# ELEC3300_DAP.net
KiCad netlist of a schematic drawn in Altium Designer
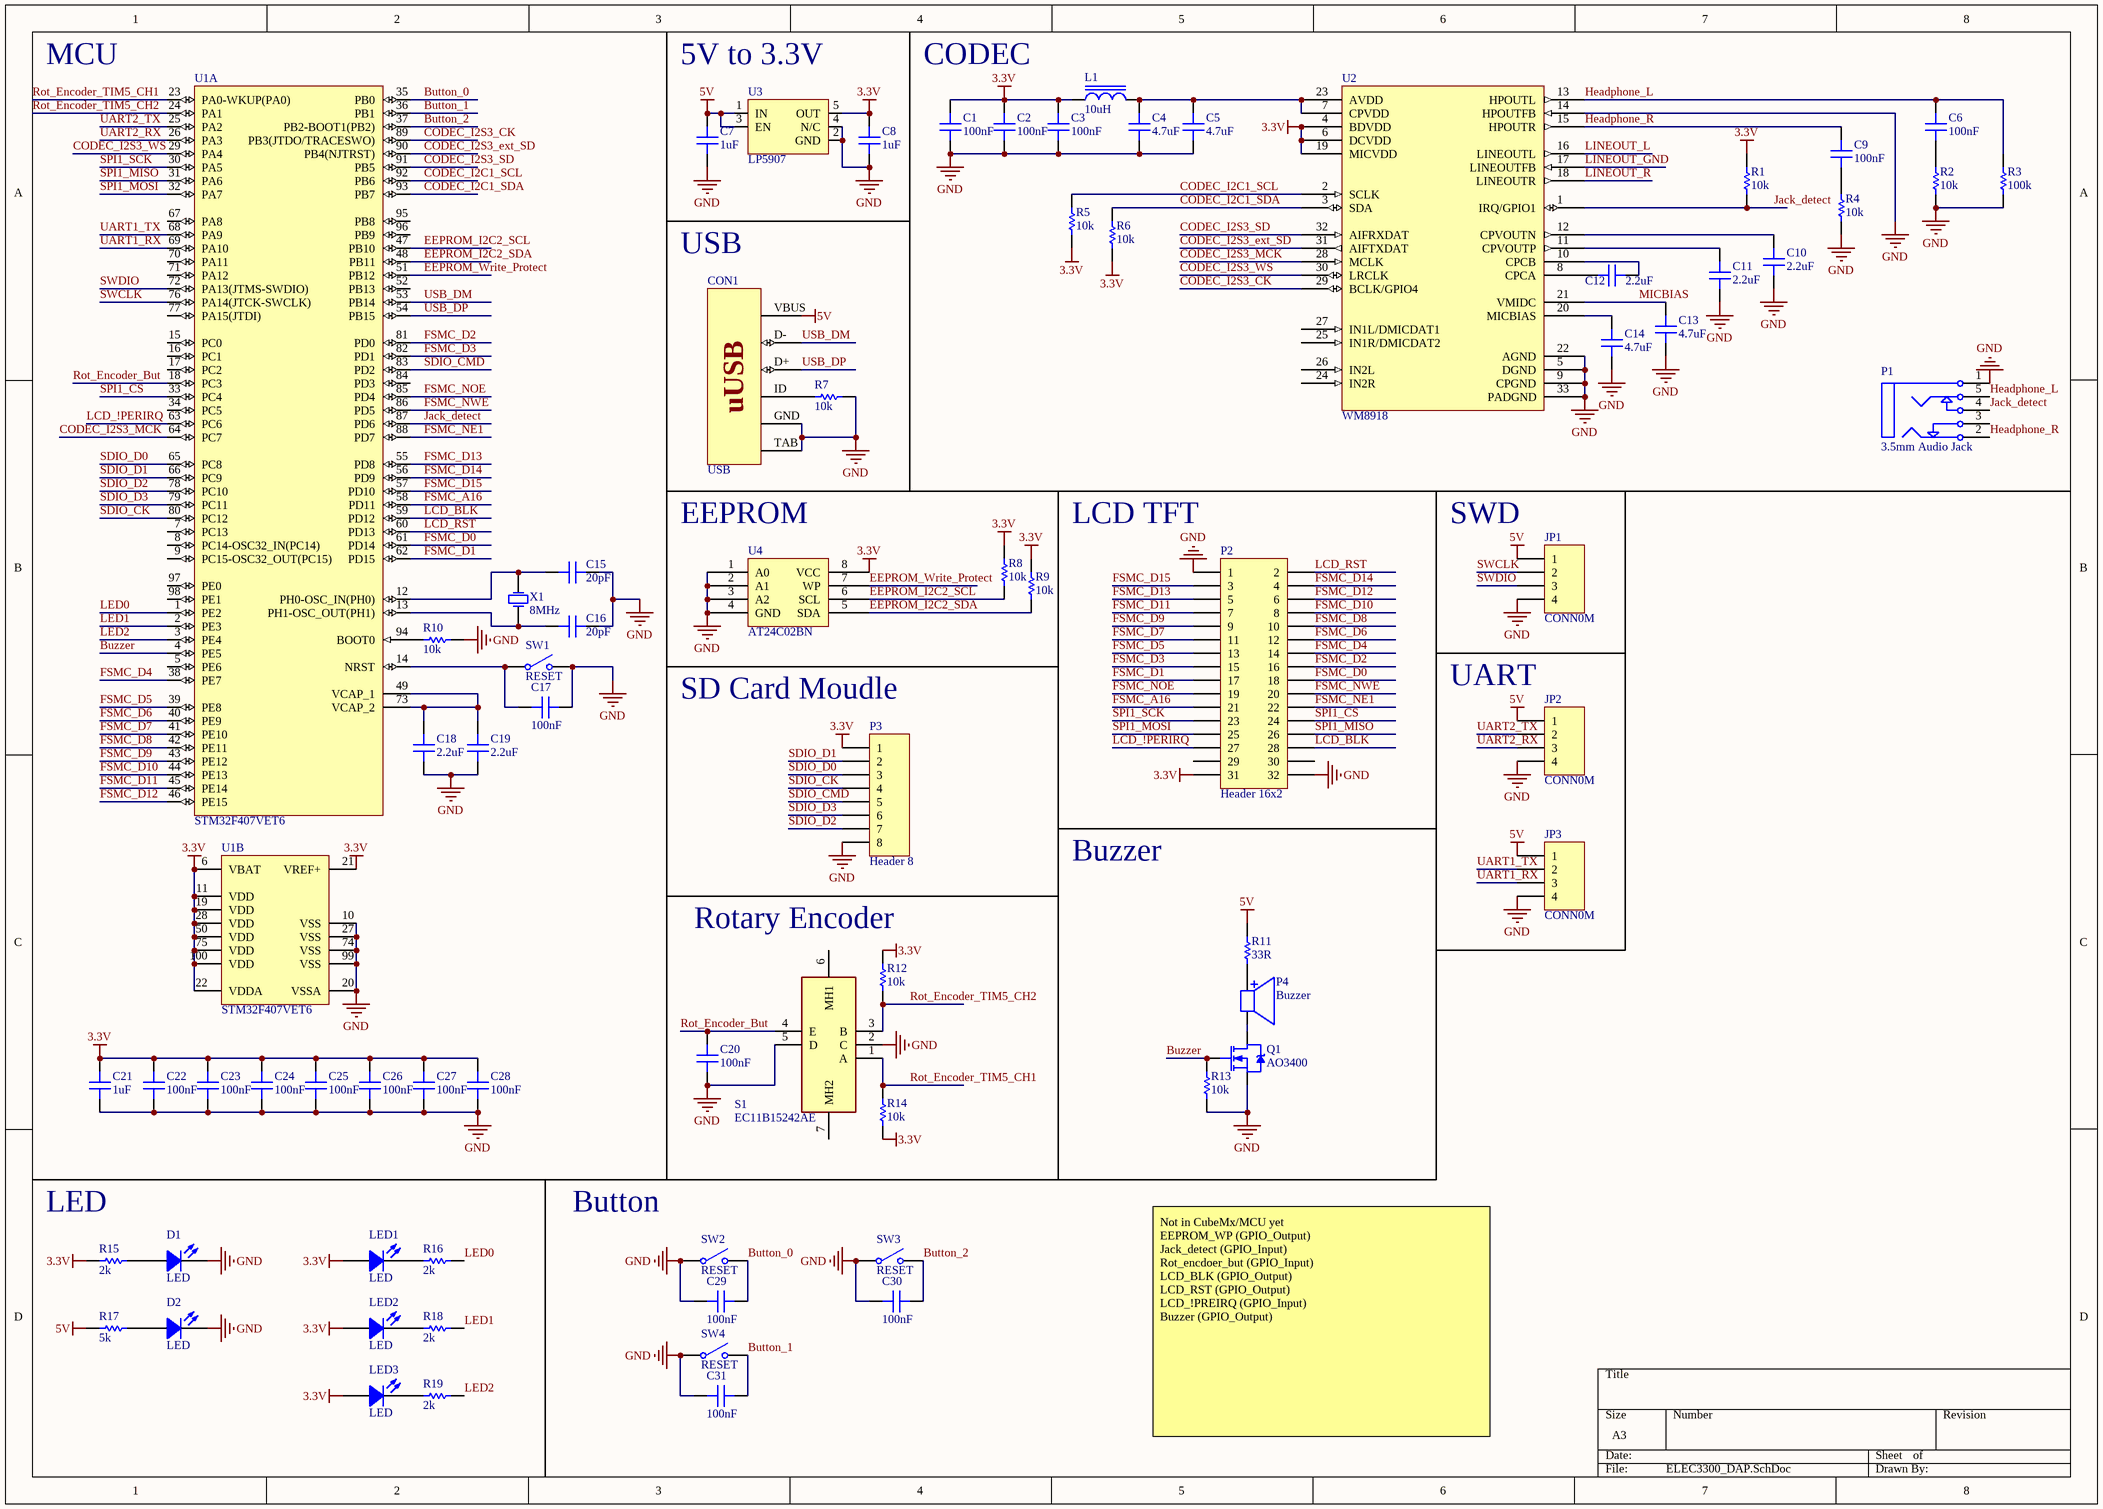
[diagram p0: ELEC3300_DAP.SchDoc]

(export (version "E")
  (design (tool "Eeschema 10.0.6"))
  (components
    (comp (ref "C1")
      (value "100nF")
      (footprint "CC2012-0805")
      (description "Capacitor (Semiconductor SIM Model)")
      (fields (field (name "PUBLISHER") "Altium Limited"))
      (libsource (lib "Robocon_RCL") (part "Cap Semi"))
    )
    (comp (ref "C2")
      (value "100nF")
      (footprint "CC2012-0805")
      (description "Capacitor (Semiconductor SIM Model)")
      (fields (field (name "PUBLISHER") "Altium Limited"))
      (libsource (lib "Robocon_RCL") (part "Cap Semi"))
    )
    (comp (ref "C3")
      (value "100nF")
      (footprint "CC2012-0805")
      (description "Capacitor (Semiconductor SIM Model)")
      (fields (field (name "PUBLISHER") "Altium Limited"))
      (libsource (lib "Robocon_RCL") (part "Cap Semi"))
    )
    (comp (ref "C4")
      (value "4.7uF")
      (footprint "CC2012-0805")
      (description "Capacitor (Semiconductor SIM Model)")
      (fields (field (name "PUBLISHER") "Altium Limited"))
      (libsource (lib "Robocon_RCL") (part "Cap Semi"))
    )
    (comp (ref "C5")
      (value "4.7uF")
      (footprint "CC2012-0805")
      (description "Capacitor (Semiconductor SIM Model)")
      (fields (field (name "PUBLISHER") "Altium Limited"))
      (libsource (lib "Robocon_RCL") (part "Cap Semi"))
    )
    (comp (ref "C6")
      (value "100nF")
      (footprint "CC2012-0805")
      (description "Capacitor (Semiconductor SIM Model)")
      (fields (field (name "PUBLISHER") "Altium Limited"))
      (libsource (lib "Robocon_RCL") (part "Cap Semi"))
    )
    (comp (ref "C7")
      (value "1uF")
      (footprint "CC2012-0805")
      (description "Capacitor (Semiconductor SIM Model)")
      (fields (field (name "PUBLISHER") "Altium Limited"))
      (libsource (lib "Robocon_RCL") (part "Cap Semi"))
    )
    (comp (ref "C8")
      (value "1uF")
      (footprint "CC2012-0805")
      (description "Capacitor (Semiconductor SIM Model)")
      (fields (field (name "PUBLISHER") "Altium Limited"))
      (libsource (lib "Robocon_RCL") (part "Cap Semi"))
    )
    (comp (ref "C9")
      (value "100nF")
      (footprint "CC2012-0805")
      (description "Capacitor (Semiconductor SIM Model)")
      (fields (field (name "PUBLISHER") "Altium Limited"))
      (libsource (lib "Robocon_RCL") (part "Cap Semi"))
    )
    (comp (ref "C10")
      (value "2.2uF")
      (footprint "CC2012-0805")
      (description "Capacitor (Semiconductor SIM Model)")
      (fields (field (name "PUBLISHER") "Altium Limited"))
      (libsource (lib "Robocon_RCL") (part "Cap Semi"))
    )
    (comp (ref "C11")
      (value "2.2uF")
      (footprint "CC2012-0805")
      (description "Capacitor (Semiconductor SIM Model)")
      (fields (field (name "PUBLISHER") "Altium Limited"))
      (libsource (lib "Robocon_RCL") (part "Cap Semi"))
    )
    (comp (ref "C12")
      (value "2.2uF")
      (footprint "CC2012-0805")
      (description "Capacitor (Semiconductor SIM Model)")
      (fields (field (name "PUBLISHER") "Altium Limited"))
      (libsource (lib "Robocon_RCL") (part "Cap Semi"))
    )
    (comp (ref "C13")
      (value "4.7uF")
      (footprint "CC2012-0805")
      (description "Capacitor (Semiconductor SIM Model)")
      (fields (field (name "PUBLISHER") "Altium Limited"))
      (libsource (lib "Robocon_RCL") (part "Cap Semi"))
    )
    (comp (ref "C14")
      (value "4.7uF")
      (footprint "CC2012-0805")
      (description "Capacitor (Semiconductor SIM Model)")
      (fields (field (name "PUBLISHER") "Altium Limited"))
      (libsource (lib "Robocon_RCL") (part "Cap Semi"))
    )
    (comp (ref "C15")
      (value "20pF")
      (footprint "CC2012-0805")
      (description "Capacitor (Semiconductor SIM Model)")
      (fields (field (name "PUBLISHER") "Altium Limited"))
      (libsource (lib "Robocon_RCL") (part "Cap Semi"))
    )
    (comp (ref "C16")
      (value "20pF")
      (footprint "CC2012-0805")
      (description "Capacitor (Semiconductor SIM Model)")
      (fields (field (name "PUBLISHER") "Altium Limited"))
      (libsource (lib "Robocon_RCL") (part "Cap Semi"))
    )
    (comp (ref "C17")
      (value "100nF")
      (footprint "CC2012-0805")
      (description "Capacitor (Semiconductor SIM Model)")
      (fields (field (name "PUBLISHER") "Altium Limited"))
      (libsource (lib "Robocon_RCL") (part "Cap Semi"))
    )
    (comp (ref "C18")
      (value "2.2uF")
      (footprint "CC2012-0805")
      (description "Capacitor (Semiconductor SIM Model)")
      (fields (field (name "PUBLISHER") "Altium Limited"))
      (libsource (lib "Robocon_RCL") (part "Cap Semi"))
    )
    (comp (ref "C19")
      (value "2.2uF")
      (footprint "CC2012-0805")
      (description "Capacitor (Semiconductor SIM Model)")
      (fields (field (name "PUBLISHER") "Altium Limited"))
      (libsource (lib "Robocon_RCL") (part "Cap Semi"))
    )
    (comp (ref "C20")
      (value "100nF")
      (footprint "CC2012-0805")
      (description "Capacitor (Semiconductor SIM Model)")
      (fields (field (name "PUBLISHER") "Altium Limited"))
      (libsource (lib "Robocon_RCL") (part "Cap Semi"))
    )
    (comp (ref "C21")
      (value "1uF")
      (footprint "CC2012-0805")
      (description "Capacitor (Semiconductor SIM Model)")
      (fields (field (name "PUBLISHER") "Altium Limited"))
      (libsource (lib "Robocon_RCL") (part "Cap Semi"))
    )
    (comp (ref "C22")
      (value "100nF")
      (footprint "CC2012-0805")
      (description "Capacitor (Semiconductor SIM Model)")
      (fields (field (name "PUBLISHER") "Altium Limited"))
      (libsource (lib "Robocon_RCL") (part "Cap Semi"))
    )
    (comp (ref "C23")
      (value "100nF")
      (footprint "CC2012-0805")
      (description "Capacitor (Semiconductor SIM Model)")
      (fields (field (name "PUBLISHER") "Altium Limited"))
      (libsource (lib "Robocon_RCL") (part "Cap Semi"))
    )
    (comp (ref "C24")
      (value "100nF")
      (footprint "CC2012-0805")
      (description "Capacitor (Semiconductor SIM Model)")
      (fields (field (name "PUBLISHER") "Altium Limited"))
      (libsource (lib "Robocon_RCL") (part "Cap Semi"))
    )
    (comp (ref "C25")
      (value "100nF")
      (footprint "CC2012-0805")
      (description "Capacitor (Semiconductor SIM Model)")
      (fields (field (name "PUBLISHER") "Altium Limited"))
      (libsource (lib "Robocon_RCL") (part "Cap Semi"))
    )
    (comp (ref "C26")
      (value "100nF")
      (footprint "CC2012-0805")
      (description "Capacitor (Semiconductor SIM Model)")
      (fields (field (name "PUBLISHER") "Altium Limited"))
      (libsource (lib "Robocon_RCL") (part "Cap Semi"))
    )
    (comp (ref "C27")
      (value "100nF")
      (footprint "CC2012-0805")
      (description "Capacitor (Semiconductor SIM Model)")
      (fields (field (name "PUBLISHER") "Altium Limited"))
      (libsource (lib "Robocon_RCL") (part "Cap Semi"))
    )
    (comp (ref "C28")
      (value "100nF")
      (footprint "CC2012-0805")
      (description "Capacitor (Semiconductor SIM Model)")
      (fields (field (name "PUBLISHER") "Altium Limited"))
      (libsource (lib "Robocon_RCL") (part "Cap Semi"))
    )
    (comp (ref "C29")
      (value "100nF")
      (footprint "CC2012-0805")
      (description "Capacitor (Semiconductor SIM Model)")
      (fields (field (name "PUBLISHER") "Altium Limited"))
      (libsource (lib "Robocon_RCL") (part "Cap Semi"))
    )
    (comp (ref "C30")
      (value "100nF")
      (footprint "CC2012-0805")
      (description "Capacitor (Semiconductor SIM Model)")
      (fields (field (name "PUBLISHER") "Altium Limited"))
      (libsource (lib "Robocon_RCL") (part "Cap Semi"))
    )
    (comp (ref "C31")
      (value "100nF")
      (footprint "CC2012-0805")
      (description "Capacitor (Semiconductor SIM Model)")
      (fields (field (name "PUBLISHER") "Altium Limited"))
      (libsource (lib "Robocon_RCL") (part "Cap Semi"))
    )
    (comp (ref "CON1")
      (value "USB")
      (footprint "USB-UB-S-HML")
      (libsource (lib "Robocon_connectors") (part "USB Series Micro-B"))
    )
    (comp (ref "D1")
      (value "LED")
      (footprint "D0805")
      (description "Typical RED GaAs LED")
      (fields (field (name "PUBLISHER") "Altium Limited"))
      (libsource (lib "Robocon_BJT") (part "LED"))
    )
    (comp (ref "D2")
      (value "LED")
      (footprint "D0805")
      (description "Typical RED GaAs LED")
      (fields (field (name "PUBLISHER") "Altium Limited"))
      (libsource (lib "Robocon_BJT") (part "LED"))
    )
    (comp (ref "JP1")
      (value "CONN0M")
      (footprint "LOCKEDHDR-4W")
      (description "Header, 4-Pin")
      (fields (field (name "PUBLISHER") "Altium Limited"))
      (libsource (lib "Robocon_connectors") (part "Header 4"))
    )
    (comp (ref "JP2")
      (value "CONN0M")
      (footprint "LOCKEDHDR-4W")
      (description "Header, 4-Pin")
      (fields (field (name "PUBLISHER") "Altium Limited"))
      (libsource (lib "Robocon_connectors") (part "Header 4"))
    )
    (comp (ref "JP3")
      (value "CONN0M")
      (footprint "LOCKEDHDR-4W")
      (description "Header, 4-Pin")
      (fields (field (name "PUBLISHER") "Altium Limited"))
      (libsource (lib "Robocon_connectors") (part "Header 4"))
    )
    (comp (ref "L1")
      (value "10uH")
      (footprint "CL2012-0805")
      (description "Inductor")
      (fields (field (name "PUBLISHER") "Altium Limited"))
      (libsource (lib "Robocon_RCL") (part "Inductor"))
    )
    (comp (ref "LED1")
      (value "LED")
      (footprint "D0805")
      (description "Typical RED GaAs LED")
      (fields (field (name "PUBLISHER") "Altium Limited"))
      (libsource (lib "Robocon_BJT") (part "LED"))
    )
    (comp (ref "LED2")
      (value "LED")
      (footprint "D0805")
      (description "Typical RED GaAs LED")
      (fields (field (name "PUBLISHER") "Altium Limited"))
      (libsource (lib "Robocon_BJT") (part "LED"))
    )
    (comp (ref "LED3")
      (value "LED")
      (footprint "D0805")
      (description "Typical RED GaAs LED")
      (fields (field (name "PUBLISHER") "Altium Limited"))
      (libsource (lib "Robocon_BJT") (part "LED"))
    )
    (comp (ref "P1")
      (value "3.5mm Audio Jack")
      (footprint "STX-3120-5B")
      (description "Conductor Jack with 2 break contacts (normals) and 2 auxiliary make contacts")
      (libsource (lib "Robocon_connectors") (part "Audio Jack 3P"))
    )
    (comp (ref "P2")
      (value "Header 16x2")
      (footprint "HDR2X16")
      (libsource (lib "Schlib1") (part "Header 16x2"))
    )
    (comp (ref "P3")
      (value "Header 8")
      (footprint "HDR1X8")
      (description "Header, 8-Pin")
      (fields (field (name "PUBLISHER") "Altium Limited"))
      (libsource (lib "Robocon_connectors") (part "Header 8"))
    )
    (comp (ref "P4") (value "Buzzer") (footprint "BUZ-9.0") (libsource (lib "Robocon_RCL") (part "Buzzer")))
    (comp (ref "Q1")
      (value "AO3400")
      (footprint "SO-G3/Z3.3")
      (description "N-Channel MOSFET")
      (fields (field (name "PUBLISHER") "Altium Limited"))
      (libsource (lib "Robocon_BJT") (part "AO3400"))
    )
    (comp (ref "R1")
      (value "10k")
      (footprint "CR2012-0805")
      (description "Semiconductor Resistor")
      (fields (field (name "PUBLISHER") "Altium Limited"))
      (libsource (lib "Robocon_RCL") (part "Res Semi"))
    )
    (comp (ref "R2")
      (value "10k")
      (footprint "CR2012-0805")
      (description "Semiconductor Resistor")
      (fields (field (name "PUBLISHER") "Altium Limited"))
      (libsource (lib "Robocon_RCL") (part "Res Semi"))
    )
    (comp (ref "R3")
      (value "100k")
      (footprint "CR2012-0805")
      (description "Semiconductor Resistor")
      (fields (field (name "PUBLISHER") "Altium Limited"))
      (libsource (lib "Robocon_RCL") (part "Res Semi"))
    )
    (comp (ref "R4")
      (value "10k")
      (footprint "CR2012-0805")
      (description "Semiconductor Resistor")
      (fields (field (name "PUBLISHER") "Altium Limited"))
      (libsource (lib "Robocon_RCL") (part "Res Semi"))
    )
    (comp (ref "R5")
      (value "10k")
      (footprint "CR2012-0805")
      (description "Semiconductor Resistor")
      (fields (field (name "PUBLISHER") "Altium Limited"))
      (libsource (lib "Robocon_RCL") (part "Res Semi"))
    )
    (comp (ref "R6")
      (value "10k")
      (footprint "CR2012-0805")
      (description "Semiconductor Resistor")
      (fields (field (name "PUBLISHER") "Altium Limited"))
      (libsource (lib "Robocon_RCL") (part "Res Semi"))
    )
    (comp (ref "R7")
      (value "10k")
      (footprint "CR2012-0805")
      (description "Semiconductor Resistor")
      (fields (field (name "PUBLISHER") "Altium Limited"))
      (libsource (lib "Robocon_RCL") (part "Res Semi"))
    )
    (comp (ref "R8")
      (value "10k")
      (footprint "CR2012-0805")
      (description "Semiconductor Resistor")
      (fields (field (name "PUBLISHER") "Altium Limited"))
      (libsource (lib "Robocon_RCL") (part "Res Semi"))
    )
    (comp (ref "R9")
      (value "10k")
      (footprint "CR2012-0805")
      (description "Semiconductor Resistor")
      (fields (field (name "PUBLISHER") "Altium Limited"))
      (libsource (lib "Robocon_RCL") (part "Res Semi"))
    )
    (comp (ref "R10")
      (value "10k")
      (footprint "CR2012-0805")
      (description "Semiconductor Resistor")
      (fields (field (name "PUBLISHER") "Altium Limited"))
      (libsource (lib "Robocon_RCL") (part "Res Semi"))
    )
    (comp (ref "R11")
      (value "33R")
      (footprint "CR2012-0805")
      (description "Semiconductor Resistor")
      (fields (field (name "PUBLISHER") "Altium Limited"))
      (libsource (lib "Robocon_RCL") (part "Res Semi"))
    )
    (comp (ref "R12")
      (value "10k")
      (footprint "CR2012-0805")
      (description "Semiconductor Resistor")
      (fields (field (name "PUBLISHER") "Altium Limited"))
      (libsource (lib "Robocon_RCL") (part "Res Semi"))
    )
    (comp (ref "R13")
      (value "10k")
      (footprint "CR2012-0805")
      (description "Semiconductor Resistor")
      (fields (field (name "PUBLISHER") "Altium Limited"))
      (libsource (lib "Robocon_RCL") (part "Res Semi"))
    )
    (comp (ref "R14")
      (value "10k")
      (footprint "CR2012-0805")
      (description "Semiconductor Resistor")
      (fields (field (name "PUBLISHER") "Altium Limited"))
      (libsource (lib "Robocon_RCL") (part "Res Semi"))
    )
    (comp (ref "R15")
      (value "2k")
      (footprint "CR2012-0805")
      (description "Semiconductor Resistor")
      (fields (field (name "PUBLISHER") "Altium Limited"))
      (libsource (lib "Robocon_RCL") (part "Res Semi"))
    )
    (comp (ref "R16")
      (value "2k")
      (footprint "CR2012-0805")
      (description "Semiconductor Resistor")
      (fields (field (name "PUBLISHER") "Altium Limited"))
      (libsource (lib "Robocon_RCL") (part "Res Semi"))
    )
    (comp (ref "R17")
      (value "5k")
      (footprint "CR2012-0805")
      (description "Semiconductor Resistor")
      (fields (field (name "PUBLISHER") "Altium Limited"))
      (libsource (lib "Robocon_RCL") (part "Res Semi"))
    )
    (comp (ref "R18")
      (value "2k")
      (footprint "CR2012-0805")
      (description "Semiconductor Resistor")
      (fields (field (name "PUBLISHER") "Altium Limited"))
      (libsource (lib "Robocon_RCL") (part "Res Semi"))
    )
    (comp (ref "R19")
      (value "2k")
      (footprint "CR2012-0805")
      (description "Semiconductor Resistor")
      (fields (field (name "PUBLISHER") "Altium Limited"))
      (libsource (lib "Robocon_RCL") (part "Res Semi"))
    )
    (comp (ref "S1")
      (value "EC11B15242AE")
      (footprint "EC11B15242AE")
      (description "Switch")
      (fields (field (name "MOUSER PART NUMBER") "688-EC11B15242AE"))
      (libsource (lib "Schlib1") (part "EC11B15242AE"))
    )
    (comp (ref "SW1")
      (value "RESET")
      (footprint "PUSH SWITCH 2-PIN")
      (description "Single-Pole, Single-Throw Switch")
      (fields (field (name "PUBLISHER") "Altium Limited"))
      (libsource (lib "Robocon_connectors") (part "SW-SPST"))
    )
    (comp (ref "SW2")
      (value "RESET")
      (footprint "PUSH SWITCH")
      (description "Single-Pole, Single-Throw Switch")
      (fields (field (name "PUBLISHER") "Altium Limited"))
      (libsource (lib "Robocon_connectors") (part "SW-SPST"))
    )
    (comp (ref "SW3")
      (value "RESET")
      (footprint "PUSH SWITCH")
      (description "Single-Pole, Single-Throw Switch")
      (fields (field (name "PUBLISHER") "Altium Limited"))
      (libsource (lib "Robocon_connectors") (part "SW-SPST"))
    )
    (comp (ref "SW4")
      (value "RESET")
      (footprint "PUSH SWITCH")
      (description "Single-Pole, Single-Throw Switch")
      (fields (field (name "PUBLISHER") "Altium Limited"))
      (libsource (lib "Robocon_connectors") (part "SW-SPST"))
    )
    (comp (ref "U1")
      (value "STM32F407VET6")
      (footprint "STM-LQFP100_N")
      (fields (field (name "MANUFACTURER") "STMicroelectronics"))
      (libsource (lib "STMicroelectronics STM32 F4") (part "STM32F407VET6"))
    )
    (comp (ref "U2")
      (value "WM8918")
      (footprint "QFN40P400X400X80-33N")
      (libsource (lib "Schlib1") (part "WM8918"))
    )
    (comp (ref "U3")
      (value "LP5907")
      (footprint "SOT-23-5")
      (description "LDO\r\nInput: 2.2V to 5.5V\r\nOutput: 3.3V 250mA\r\nEnable: high volt-> turns on")
      (libsource (lib "Robocon_IC") (part "LP5907"))
    )
    (comp (ref "U4")
      (value "AT24C02BN")
      (footprint "SOP-8")
      (description "Two-wire Serial EEPROM")
      (libsource (lib "Schlib1") (part "AT24C02BN"))
    )
    (comp (ref "X1")
      (value "8MHz")
      (footprint "BCY-W2/E4.7")
      (description "Crystal Oscillator")
      (fields (field (name "PUBLISHER") "Altium Limited"))
      (libsource (lib "Robocon_RCL") (part "XTAL"))
    )
  )
  (nets
    (net (code "1") (name "/Button_0") (class "Default")
      (node (ref "C29") (pin "1") (pinfunction "1_1") (pintype "passive"))
      (node (ref "SW2") (pin "2") (pinfunction "NO_2") (pintype "passive"))
      (node (ref "U1") (pin "35") (pinfunction "PB0_35") (pintype "bidirectional"))
    )
    (net (code "2") (name "/Button_1") (class "Default")
      (node (ref "C31") (pin "1") (pinfunction "1_1") (pintype "passive"))
      (node (ref "SW4") (pin "2") (pinfunction "NO_2") (pintype "passive"))
      (node (ref "U1") (pin "36") (pinfunction "PB1_36") (pintype "bidirectional"))
    )
    (net (code "3") (name "/Button_2") (class "Default")
      (node (ref "C30") (pin "1") (pinfunction "1_1") (pintype "passive"))
      (node (ref "SW3") (pin "2") (pinfunction "NO_2") (pintype "passive"))
      (node (ref "U1") (pin "37") (pinfunction "PB2-BOOT1(PB2)_37") (pintype "bidirectional"))
    )
    (net (code "4") (name "/Buzzer") (class "Default")
      (node (ref "Q1") (pin "1") (pinfunction "G_1") (pintype "passive"))
      (node (ref "R13") (pin "2") (pinfunction "2_2") (pintype "passive"))
      (node (ref "U1") (pin "4") (pinfunction "PE5_4") (pintype "bidirectional"))
    )
    (net (code "5") (name "/CODEC_I2C1_SCL") (class "Default")
      (node (ref "R5") (pin "1") (pinfunction "1_1") (pintype "passive"))
      (node (ref "U1") (pin "92") (pinfunction "PB6_92") (pintype "bidirectional"))
      (node (ref "U2") (pin "2") (pinfunction "SCLK_2") (pintype "input"))
    )
    (net (code "6") (name "/CODEC_I2C1_SDA") (class "Default")
      (node (ref "R6") (pin "1") (pinfunction "1_1") (pintype "passive"))
      (node (ref "U1") (pin "93") (pinfunction "PB7_93") (pintype "bidirectional"))
      (node (ref "U2") (pin "3") (pinfunction "SDA_3") (pintype "bidirectional"))
    )
    (net (code "7") (name "/CODEC_I2S3_CK") (class "Default")
      (node (ref "U1") (pin "89") (pinfunction "PB3(JTDO/TRACESWO)_89") (pintype "bidirectional"))
      (node (ref "U2") (pin "29") (pinfunction "BCLK/GPIO4_29") (pintype "bidirectional"))
    )
    (net (code "8") (name "/CODEC_I2S3_MCK") (class "Default")
      (node (ref "U1") (pin "64") (pinfunction "PC7_64") (pintype "bidirectional"))
      (node (ref "U2") (pin "28") (pinfunction "MCLK_28") (pintype "input"))
    )
    (net (code "9") (name "/CODEC_I2S3_SD") (class "Default")
      (node (ref "U1") (pin "91") (pinfunction "PB5_91") (pintype "bidirectional"))
      (node (ref "U2") (pin "32") (pinfunction "AIFRXDAT_32") (pintype "input"))
    )
    (net (code "10") (name "/CODEC_I2S3_WS") (class "Default")
      (node (ref "U1") (pin "29") (pinfunction "PA4_29") (pintype "bidirectional"))
      (node (ref "U2") (pin "30") (pinfunction "LRCLK_30") (pintype "bidirectional"))
    )
    (net (code "11") (name "/CODEC_I2S3_ext_SD") (class "Default")
      (node (ref "U1") (pin "90") (pinfunction "PB4(NJTRST)_90") (pintype "bidirectional"))
      (node (ref "U2") (pin "31") (pinfunction "AIFTXDAT_31") (pintype "output"))
    )
    (net (code "12") (name "/EEPROM_I2C2_SCL") (class "Default")
      (node (ref "R8") (pin "1") (pinfunction "1_1") (pintype "passive"))
      (node (ref "U1") (pin "47") (pinfunction "PB10_47") (pintype "bidirectional"))
      (node (ref "U4") (pin "6") (pinfunction "SCL_6") (pintype "passive"))
    )
    (net (code "13") (name "/EEPROM_I2C2_SDA") (class "Default")
      (node (ref "R9") (pin "1") (pinfunction "1_1") (pintype "passive"))
      (node (ref "U1") (pin "48") (pinfunction "PB11_48") (pintype "bidirectional"))
      (node (ref "U4") (pin "5") (pinfunction "SDA_5") (pintype "passive"))
    )
    (net (code "14") (name "/EEPROM_Write_Protect") (class "Default")
      (node (ref "U1") (pin "51") (pinfunction "PB12_51") (pintype "bidirectional"))
      (node (ref "U4") (pin "7") (pinfunction "WP_7") (pintype "passive"))
    )
    (net (code "15") (name "/FSMC_A16") (class "Default")
      (node (ref "P2") (pin "21") (pinfunction "21_21") (pintype "passive"))
      (node (ref "U1") (pin "58") (pinfunction "PD11_58") (pintype "bidirectional"))
    )
    (net (code "16") (name "/FSMC_D0") (class "Default")
      (node (ref "P2") (pin "18") (pinfunction "18_18") (pintype "passive"))
      (node (ref "U1") (pin "61") (pinfunction "PD14_61") (pintype "bidirectional"))
    )
    (net (code "17") (name "/FSMC_D1") (class "Default")
      (node (ref "P2") (pin "17") (pinfunction "17_17") (pintype "passive"))
      (node (ref "U1") (pin "62") (pinfunction "PD15_62") (pintype "bidirectional"))
    )
    (net (code "18") (name "/FSMC_D2") (class "Default")
      (node (ref "P2") (pin "16") (pinfunction "16_16") (pintype "passive"))
      (node (ref "U1") (pin "81") (pinfunction "PD0_81") (pintype "bidirectional"))
    )
    (net (code "19") (name "/FSMC_D3") (class "Default")
      (node (ref "P2") (pin "15") (pinfunction "15_15") (pintype "passive"))
      (node (ref "U1") (pin "82") (pinfunction "PD1_82") (pintype "bidirectional"))
    )
    (net (code "20") (name "/FSMC_D4") (class "Default")
      (node (ref "P2") (pin "14") (pinfunction "14_14") (pintype "passive"))
      (node (ref "U1") (pin "38") (pinfunction "PE7_38") (pintype "bidirectional"))
    )
    (net (code "21") (name "/FSMC_D5") (class "Default")
      (node (ref "P2") (pin "13") (pinfunction "13_13") (pintype "passive"))
      (node (ref "U1") (pin "39") (pinfunction "PE8_39") (pintype "bidirectional"))
    )
    (net (code "22") (name "/FSMC_D6") (class "Default")
      (node (ref "P2") (pin "12") (pinfunction "12_12") (pintype "passive"))
      (node (ref "U1") (pin "40") (pinfunction "PE9_40") (pintype "bidirectional"))
    )
    (net (code "23") (name "/FSMC_D7") (class "Default")
      (node (ref "P2") (pin "11") (pinfunction "11_11") (pintype "passive"))
      (node (ref "U1") (pin "41") (pinfunction "PE10_41") (pintype "bidirectional"))
    )
    (net (code "24") (name "/FSMC_D8") (class "Default")
      (node (ref "P2") (pin "10") (pinfunction "10_10") (pintype "passive"))
      (node (ref "U1") (pin "42") (pinfunction "PE11_42") (pintype "bidirectional"))
    )
    (net (code "25") (name "/FSMC_D9") (class "Default")
      (node (ref "P2") (pin "9") (pinfunction "9_9") (pintype "passive"))
      (node (ref "U1") (pin "43") (pinfunction "PE12_43") (pintype "bidirectional"))
    )
    (net (code "26") (name "/FSMC_D10") (class "Default")
      (node (ref "P2") (pin "8") (pinfunction "8_8") (pintype "passive"))
      (node (ref "U1") (pin "44") (pinfunction "PE13_44") (pintype "bidirectional"))
    )
    (net (code "27") (name "/FSMC_D11") (class "Default")
      (node (ref "P2") (pin "7") (pinfunction "7_7") (pintype "passive"))
      (node (ref "U1") (pin "45") (pinfunction "PE14_45") (pintype "bidirectional"))
    )
    (net (code "28") (name "/FSMC_D12") (class "Default")
      (node (ref "P2") (pin "6") (pinfunction "6_6") (pintype "passive"))
      (node (ref "U1") (pin "46") (pinfunction "PE15_46") (pintype "bidirectional"))
    )
    (net (code "29") (name "/FSMC_D13") (class "Default")
      (node (ref "P2") (pin "5") (pinfunction "5_5") (pintype "passive"))
      (node (ref "U1") (pin "55") (pinfunction "PD8_55") (pintype "bidirectional"))
    )
    (net (code "30") (name "/FSMC_D14") (class "Default")
      (node (ref "P2") (pin "4") (pinfunction "4_4") (pintype "passive"))
      (node (ref "U1") (pin "56") (pinfunction "PD9_56") (pintype "bidirectional"))
    )
    (net (code "31") (name "/FSMC_D15") (class "Default")
      (node (ref "P2") (pin "3") (pinfunction "3_3") (pintype "passive"))
      (node (ref "U1") (pin "57") (pinfunction "PD10_57") (pintype "bidirectional"))
    )
    (net (code "32") (name "/FSMC_NE1") (class "Default")
      (node (ref "P2") (pin "22") (pinfunction "22_22") (pintype "passive"))
      (node (ref "U1") (pin "88") (pinfunction "PD7_88") (pintype "bidirectional"))
    )
    (net (code "33") (name "/FSMC_NOE") (class "Default")
      (node (ref "P2") (pin "19") (pinfunction "19_19") (pintype "passive"))
      (node (ref "U1") (pin "85") (pinfunction "PD4_85") (pintype "bidirectional"))
    )
    (net (code "34") (name "/FSMC_NWE") (class "Default")
      (node (ref "P2") (pin "20") (pinfunction "20_20") (pintype "passive"))
      (node (ref "U1") (pin "86") (pinfunction "PD5_86") (pintype "bidirectional"))
    )
    (net (code "35") (name "/Headphone_L") (class "Default")
      (node (ref "C6") (pin "2") (pinfunction "2_2") (pintype "passive"))
      (node (ref "P1") (pin "5") (pinfunction "5_5") (pintype "passive"))
      (node (ref "R3") (pin "2") (pinfunction "2_2") (pintype "passive"))
      (node (ref "U2") (pin "13") (pinfunction "HPOUTL_13") (pintype "output"))
    )
    (net (code "36") (name "/Headphone_R") (class "Default")
      (node (ref "C9") (pin "2") (pinfunction "2_2") (pintype "passive"))
      (node (ref "P1") (pin "2") (pinfunction "2_2") (pintype "passive"))
      (node (ref "U2") (pin "15") (pinfunction "HPOUTR_15") (pintype "output"))
    )
    (net (code "37") (name "/Jack_detect") (class "Default")
      (node (ref "P1") (pin "4") (pinfunction "4_4") (pintype "passive"))
      (node (ref "R1") (pin "2") (pinfunction "2_2") (pintype "passive"))
      (node (ref "U1") (pin "87") (pinfunction "PD6_87") (pintype "bidirectional"))
      (node (ref "U2") (pin "1") (pinfunction "IRQ/GPIO1_1") (pintype "bidirectional"))
    )
    (net (code "38") (name "/LCD_!PERIRQ") (class "Default")
      (node (ref "P2") (pin "27") (pinfunction "27_27") (pintype "passive"))
      (node (ref "U1") (pin "63") (pinfunction "PC6_63") (pintype "bidirectional"))
    )
    (net (code "39") (name "/LCD_BLK") (class "Default")
      (node (ref "P2") (pin "28") (pinfunction "28_28") (pintype "passive"))
      (node (ref "U1") (pin "59") (pinfunction "PD12_59") (pintype "bidirectional"))
    )
    (net (code "40") (name "/LCD_RST") (class "Default")
      (node (ref "P2") (pin "2") (pinfunction "2_2") (pintype "passive"))
      (node (ref "U1") (pin "60") (pinfunction "PD13_60") (pintype "bidirectional"))
    )
    (net (code "41") (name "/LED0") (class "Default")
      (node (ref "R16") (pin "2") (pinfunction "2_2") (pintype "passive"))
      (node (ref "U1") (pin "1") (pinfunction "PE2_1") (pintype "bidirectional"))
    )
    (net (code "42") (name "/LED1") (class "Default")
      (node (ref "R18") (pin "2") (pinfunction "2_2") (pintype "passive"))
      (node (ref "U1") (pin "2") (pinfunction "PE3_2") (pintype "bidirectional"))
    )
    (net (code "43") (name "/LED2") (class "Default")
      (node (ref "R19") (pin "2") (pinfunction "2_2") (pintype "passive"))
      (node (ref "U1") (pin "3") (pinfunction "PE4_3") (pintype "bidirectional"))
    )
    (net (code "44") (name "/LINEOUT_GND") (class "Default")
      (node (ref "U2") (pin "17") (pinfunction "LINEOUTFB_17") (pintype "input"))
    )
    (net (code "45") (name "/LINEOUT_L") (class "Default")
      (node (ref "U2") (pin "16") (pinfunction "LINEOUTL_16") (pintype "output"))
    )
    (net (code "46") (name "/LINEOUT_R") (class "Default")
      (node (ref "U2") (pin "18") (pinfunction "LINEOUTR_18") (pintype "output"))
    )
    (net (code "47") (name "/MICBIAS") (class "Default")
      (node (ref "C13") (pin "2") (pinfunction "2_2") (pintype "passive"))
      (node (ref "U2") (pin "21") (pinfunction "VMIDC_21") (pintype "power_in"))
    )
    (net (code "48") (name "/Rot_Encoder_But") (class "Default")
      (node (ref "C20") (pin "1") (pinfunction "1_1") (pintype "passive"))
      (node (ref "S1") (pin "4") (pinfunction "E_4") (pintype "passive"))
      (node (ref "U1") (pin "18") (pinfunction "PC3_18") (pintype "bidirectional"))
    )
    (net (code "49") (name "/Rot_Encoder_TIM5_CH1") (class "Default")
      (node (ref "R14") (pin "2") (pinfunction "2_2") (pintype "passive"))
      (node (ref "S1") (pin "1") (pinfunction "A_1") (pintype "passive"))
      (node (ref "U1") (pin "23") (pinfunction "PA0-WKUP(PA0)_23") (pintype "bidirectional"))
    )
    (net (code "50") (name "/Rot_Encoder_TIM5_CH2") (class "Default")
      (node (ref "R12") (pin "1") (pinfunction "1_1") (pintype "passive"))
      (node (ref "S1") (pin "3") (pinfunction "B_3") (pintype "passive"))
      (node (ref "U1") (pin "24") (pinfunction "PA1_24") (pintype "bidirectional"))
    )
    (net (code "51") (name "/SDIO_CK") (class "Default")
      (node (ref "P3") (pin "4") (pinfunction "4_4") (pintype "passive"))
      (node (ref "U1") (pin "80") (pinfunction "PC12_80") (pintype "bidirectional"))
    )
    (net (code "52") (name "/SDIO_CMD") (class "Default")
      (node (ref "P3") (pin "5") (pinfunction "5_5") (pintype "passive"))
      (node (ref "U1") (pin "83") (pinfunction "PD2_83") (pintype "bidirectional"))
    )
    (net (code "53") (name "/SDIO_D0") (class "Default")
      (node (ref "P3") (pin "3") (pinfunction "3_3") (pintype "passive"))
      (node (ref "U1") (pin "65") (pinfunction "PC8_65") (pintype "bidirectional"))
    )
    (net (code "54") (name "/SDIO_D1") (class "Default")
      (node (ref "P3") (pin "2") (pinfunction "2_2") (pintype "passive"))
      (node (ref "U1") (pin "66") (pinfunction "PC9_66") (pintype "bidirectional"))
    )
    (net (code "55") (name "/SDIO_D2") (class "Default")
      (node (ref "P3") (pin "7") (pinfunction "7_7") (pintype "passive"))
      (node (ref "U1") (pin "78") (pinfunction "PC10_78") (pintype "bidirectional"))
    )
    (net (code "56") (name "/SDIO_D3") (class "Default")
      (node (ref "P3") (pin "6") (pinfunction "6_6") (pintype "passive"))
      (node (ref "U1") (pin "79") (pinfunction "PC11_79") (pintype "bidirectional"))
    )
    (net (code "57") (name "/SPI1_CS") (class "Default")
      (node (ref "P2") (pin "24") (pinfunction "24_24") (pintype "passive"))
      (node (ref "U1") (pin "33") (pinfunction "PC4_33") (pintype "bidirectional"))
    )
    (net (code "58") (name "/SPI1_MISO") (class "Default")
      (node (ref "P2") (pin "26") (pinfunction "26_26") (pintype "passive"))
      (node (ref "U1") (pin "31") (pinfunction "PA6_31") (pintype "bidirectional"))
    )
    (net (code "59") (name "/SPI1_MOSI") (class "Default")
      (node (ref "P2") (pin "25") (pinfunction "25_25") (pintype "passive"))
      (node (ref "U1") (pin "32") (pinfunction "PA7_32") (pintype "bidirectional"))
    )
    (net (code "60") (name "/SPI1_SCK") (class "Default")
      (node (ref "P2") (pin "23") (pinfunction "23_23") (pintype "passive"))
      (node (ref "U1") (pin "30") (pinfunction "PA5_30") (pintype "bidirectional"))
    )
    (net (code "61") (name "/SWCLK") (class "Default")
      (node (ref "JP1") (pin "2") (pinfunction "2_2") (pintype "passive"))
      (node (ref "U1") (pin "76") (pinfunction "PA14(JTCK-SWCLK)_76") (pintype "bidirectional"))
    )
    (net (code "62") (name "/SWDIO") (class "Default")
      (node (ref "JP1") (pin "3") (pinfunction "3_3") (pintype "passive"))
      (node (ref "U1") (pin "72") (pinfunction "PA13(JTMS-SWDIO)_72") (pintype "bidirectional"))
    )
    (net (code "63") (name "/UART1_RX") (class "Default")
      (node (ref "JP3") (pin "3") (pinfunction "3_3") (pintype "passive"))
      (node (ref "U1") (pin "69") (pinfunction "PA10_69") (pintype "bidirectional"))
    )
    (net (code "64") (name "/UART1_TX") (class "Default")
      (node (ref "JP3") (pin "2") (pinfunction "2_2") (pintype "passive"))
      (node (ref "U1") (pin "68") (pinfunction "PA9_68") (pintype "bidirectional"))
    )
    (net (code "65") (name "/UART2_RX") (class "Default")
      (node (ref "JP2") (pin "3") (pinfunction "3_3") (pintype "passive"))
      (node (ref "U1") (pin "26") (pinfunction "PA3_26") (pintype "bidirectional"))
    )
    (net (code "66") (name "/UART2_TX") (class "Default")
      (node (ref "JP2") (pin "2") (pinfunction "2_2") (pintype "passive"))
      (node (ref "U1") (pin "25") (pinfunction "PA2_25") (pintype "bidirectional"))
    )
    (net (code "67") (name "/USB_DM") (class "Default")
      (node (ref "CON1") (pin "D-") (pintype "bidirectional"))
      (node (ref "U1") (pin "53") (pinfunction "PB14_53") (pintype "bidirectional"))
    )
    (net (code "68") (name "/USB_DP") (class "Default")
      (node (ref "CON1") (pin "D+") (pintype "bidirectional"))
      (node (ref "U1") (pin "54") (pinfunction "PB15_54") (pintype "bidirectional"))
    )
    (net (code "69") (name "3.3V") (class "Default")
      (node (ref "C1") (pin "2") (pinfunction "2_2") (pintype "passive"))
      (node (ref "C2") (pin "2") (pinfunction "2_2") (pintype "passive"))
      (node (ref "C21") (pin "2") (pinfunction "2_2") (pintype "passive"))
      (node (ref "C22") (pin "2") (pinfunction "2_2") (pintype "passive"))
      (node (ref "C23") (pin "2") (pinfunction "2_2") (pintype "passive"))
      (node (ref "C24") (pin "2") (pinfunction "2_2") (pintype "passive"))
      (node (ref "C25") (pin "2") (pinfunction "2_2") (pintype "passive"))
      (node (ref "C26") (pin "2") (pinfunction "2_2") (pintype "passive"))
      (node (ref "C27") (pin "2") (pinfunction "2_2") (pintype "passive"))
      (node (ref "C28") (pin "2") (pinfunction "2_2") (pintype "passive"))
      (node (ref "C3") (pin "2") (pinfunction "2_2") (pintype "passive"))
      (node (ref "C8") (pin "2") (pinfunction "2_2") (pintype "passive"))
      (node (ref "L1") (pin "1") (pinfunction "1_1") (pintype "passive"))
      (node (ref "LED1") (pin "1") (pinfunction "A_1") (pintype "passive"))
      (node (ref "LED2") (pin "1") (pinfunction "A_1") (pintype "passive"))
      (node (ref "LED3") (pin "1") (pinfunction "A_1") (pintype "passive"))
      (node (ref "P2") (pin "31") (pinfunction "31_31") (pintype "passive"))
      (node (ref "P3") (pin "1") (pinfunction "1_1") (pintype "passive"))
      (node (ref "R1") (pin "1") (pinfunction "1_1") (pintype "passive"))
      (node (ref "R12") (pin "2") (pinfunction "2_2") (pintype "passive"))
      (node (ref "R14") (pin "1") (pinfunction "1_1") (pintype "passive"))
      (node (ref "R15") (pin "1") (pinfunction "1_1") (pintype "passive"))
      (node (ref "R5") (pin "2") (pinfunction "2_2") (pintype "passive"))
      (node (ref "R6") (pin "2") (pinfunction "2_2") (pintype "passive"))
      (node (ref "R8") (pin "2") (pinfunction "2_2") (pintype "passive"))
      (node (ref "R9") (pin "2") (pinfunction "2_2") (pintype "passive"))
      (node (ref "U1") (pin "100") (pinfunction "VDD_100") (pintype "power_in"))
      (node (ref "U1") (pin "11") (pinfunction "VDD_11") (pintype "power_in"))
      (node (ref "U1") (pin "19") (pinfunction "VDD_19") (pintype "power_in"))
      (node (ref "U1") (pin "21") (pinfunction "VREF+_21") (pintype "power_in"))
      (node (ref "U1") (pin "22") (pinfunction "VDDA_22") (pintype "power_in"))
      (node (ref "U1") (pin "28") (pinfunction "VDD_28") (pintype "power_in"))
      (node (ref "U1") (pin "50") (pinfunction "VDD_50") (pintype "power_in"))
      (node (ref "U1") (pin "6") (pinfunction "VBAT_6") (pintype "power_in"))
      (node (ref "U1") (pin "75") (pinfunction "VDD_75") (pintype "power_in"))
      (node (ref "U2") (pin "19") (pinfunction "MICVDD_19") (pintype "power_in"))
      (node (ref "U2") (pin "4") (pinfunction "BDVDD_4") (pintype "power_in"))
      (node (ref "U2") (pin "6") (pinfunction "DCVDD_6") (pintype "power_in"))
      (node (ref "U3") (pin "5") (pinfunction "OUT_5") (pintype "passive"))
      (node (ref "U4") (pin "8") (pinfunction "VCC_8") (pintype "passive"))
    )
    (net (code "70") (name "5V") (class "Default")
      (node (ref "C7") (pin "2") (pinfunction "2_2") (pintype "passive"))
      (node (ref "CON1") (pin "VBUS") (pintype "power_in"))
      (node (ref "JP1") (pin "1") (pinfunction "1_1") (pintype "passive"))
      (node (ref "JP2") (pin "1") (pinfunction "1_1") (pintype "passive"))
      (node (ref "JP3") (pin "1") (pinfunction "1_1") (pintype "passive"))
      (node (ref "R11") (pin "2") (pinfunction "2_2") (pintype "passive"))
      (node (ref "R17") (pin "1") (pinfunction "1_1") (pintype "passive"))
      (node (ref "U3") (pin "1") (pinfunction "IN_1") (pintype "passive"))
      (node (ref "U3") (pin "3") (pinfunction "EN_3") (pintype "passive"))
    )
    (net (code "71") (name "GND") (class "Default")
      (node (ref "C1") (pin "1") (pinfunction "1_1") (pintype "passive"))
      (node (ref "C10") (pin "2") (pinfunction "2_2") (pintype "passive"))
      (node (ref "C11") (pin "1") (pinfunction "1_1") (pintype "passive"))
      (node (ref "C13") (pin "1") (pinfunction "1_1") (pintype "passive"))
      (node (ref "C14") (pin "1") (pinfunction "1_1") (pintype "passive"))
      (node (ref "C15") (pin "2") (pinfunction "2_2") (pintype "passive"))
      (node (ref "C16") (pin "2") (pinfunction "2_2") (pintype "passive"))
      (node (ref "C17") (pin "2") (pinfunction "2_2") (pintype "passive"))
      (node (ref "C18") (pin "1") (pinfunction "1_1") (pintype "passive"))
      (node (ref "C19") (pin "1") (pinfunction "1_1") (pintype "passive"))
      (node (ref "C2") (pin "1") (pinfunction "1_1") (pintype "passive"))
      (node (ref "C20") (pin "2") (pinfunction "2_2") (pintype "passive"))
      (node (ref "C21") (pin "1") (pinfunction "1_1") (pintype "passive"))
      (node (ref "C22") (pin "1") (pinfunction "1_1") (pintype "passive"))
      (node (ref "C23") (pin "1") (pinfunction "1_1") (pintype "passive"))
      (node (ref "C24") (pin "1") (pinfunction "1_1") (pintype "passive"))
      (node (ref "C25") (pin "1") (pinfunction "1_1") (pintype "passive"))
      (node (ref "C26") (pin "1") (pinfunction "1_1") (pintype "passive"))
      (node (ref "C27") (pin "1") (pinfunction "1_1") (pintype "passive"))
      (node (ref "C28") (pin "1") (pinfunction "1_1") (pintype "passive"))
      (node (ref "C29") (pin "2") (pinfunction "2_2") (pintype "passive"))
      (node (ref "C3") (pin "1") (pinfunction "1_1") (pintype "passive"))
      (node (ref "C30") (pin "2") (pinfunction "2_2") (pintype "passive"))
      (node (ref "C31") (pin "2") (pinfunction "2_2") (pintype "passive"))
      (node (ref "C4") (pin "1") (pinfunction "1_1") (pintype "passive"))
      (node (ref "C5") (pin "1") (pinfunction "1_1") (pintype "passive"))
      (node (ref "C7") (pin "1") (pinfunction "1_1") (pintype "passive"))
      (node (ref "C8") (pin "1") (pinfunction "1_1") (pintype "passive"))
      (node (ref "CON1") (pin "GND") (pintype "power_in"))
      (node (ref "CON1") (pin "TAB") (pintype "power_in"))
      (node (ref "D1") (pin "2") (pinfunction "K_2") (pintype "passive"))
      (node (ref "D2") (pin "2") (pinfunction "K_2") (pintype "passive"))
      (node (ref "JP1") (pin "4") (pinfunction "4_4") (pintype "passive"))
      (node (ref "JP2") (pin "4") (pinfunction "4_4") (pintype "passive"))
      (node (ref "JP3") (pin "4") (pinfunction "4_4") (pintype "passive"))
      (node (ref "P1") (pin "1") (pinfunction "1_1") (pintype "passive"))
      (node (ref "P2") (pin "1") (pinfunction "1_1") (pintype "passive"))
      (node (ref "P2") (pin "32") (pinfunction "32_32") (pintype "passive"))
      (node (ref "P3") (pin "8") (pinfunction "8_8") (pintype "passive"))
      (node (ref "Q1") (pin "2") (pinfunction "S_2") (pintype "passive"))
      (node (ref "R10") (pin "2") (pinfunction "2_2") (pintype "passive"))
      (node (ref "R13") (pin "1") (pinfunction "1_1") (pintype "passive"))
      (node (ref "R2") (pin "1") (pinfunction "1_1") (pintype "passive"))
      (node (ref "R3") (pin "1") (pinfunction "1_1") (pintype "passive"))
      (node (ref "R4") (pin "1") (pinfunction "1_1") (pintype "passive"))
      (node (ref "R7") (pin "2") (pinfunction "2_2") (pintype "passive"))
      (node (ref "S1") (pin "2") (pinfunction "C_2") (pintype "passive"))
      (node (ref "S1") (pin "5") (pinfunction "D_5") (pintype "passive"))
      (node (ref "SW1") (pin "2") (pinfunction "NO_2") (pintype "passive"))
      (node (ref "SW2") (pin "1") (pinfunction "COMMON_1") (pintype "passive"))
      (node (ref "SW3") (pin "1") (pinfunction "COMMON_1") (pintype "passive"))
      (node (ref "SW4") (pin "1") (pinfunction "COMMON_1") (pintype "passive"))
      (node (ref "U1") (pin "10") (pinfunction "VSS_10") (pintype "power_in"))
      (node (ref "U1") (pin "20") (pinfunction "VSSA_20") (pintype "power_in"))
      (node (ref "U1") (pin "27") (pinfunction "VSS_27") (pintype "power_in"))
      (node (ref "U1") (pin "74") (pinfunction "VSS_74") (pintype "power_in"))
      (node (ref "U1") (pin "99") (pinfunction "VSS_99") (pintype "power_in"))
      (node (ref "U2") (pin "14") (pinfunction "HPOUTFB_14") (pintype "input"))
      (node (ref "U2") (pin "22") (pinfunction "AGND_22") (pintype "power_in"))
      (node (ref "U2") (pin "33") (pinfunction "PADGND_33") (pintype "power_in"))
      (node (ref "U2") (pin "5") (pinfunction "DGND_5") (pintype "power_in"))
      (node (ref "U2") (pin "9") (pinfunction "CPGND_9") (pintype "power_in"))
      (node (ref "U3") (pin "2") (pinfunction "GND_2") (pintype "passive"))
      (node (ref "U3") (pin "4") (pinfunction "N/C_4") (pintype "passive"))
      (node (ref "U4") (pin "1") (pinfunction "A0_1") (pintype "passive"))
      (node (ref "U4") (pin "2") (pinfunction "A1_2") (pintype "passive"))
      (node (ref "U4") (pin "3") (pinfunction "A2_3") (pintype "passive"))
      (node (ref "U4") (pin "4") (pinfunction "GND_4") (pintype "power_in"))
    )
    (net (code "72") (name "Net-(C6-Pad1)") (class "Default")
      (node (ref "C6") (pin "1") (pinfunction "1_1") (pintype "passive"))
      (node (ref "R2") (pin "2") (pinfunction "2_2") (pintype "passive"))
    )
    (net (code "73") (name "Net-(C9-Pad1)") (class "Default")
      (node (ref "C9") (pin "1") (pinfunction "1_1") (pintype "passive"))
      (node (ref "R4") (pin "2") (pinfunction "2_2") (pintype "passive"))
    )
    (net (code "74") (name "Net-(CON1-PadID)") (class "Default")
      (node (ref "CON1") (pin "ID") (pintype "passive"))
      (node (ref "R7") (pin "1") (pinfunction "1_1") (pintype "passive"))
    )
    (net (code "75") (name "Net-(D1-A)") (class "Default")
      (node (ref "D1") (pin "1") (pinfunction "A_1") (pintype "passive"))
      (node (ref "R15") (pin "2") (pinfunction "2_2") (pintype "passive"))
    )
    (net (code "76") (name "Net-(D2-A)") (class "Default")
      (node (ref "D2") (pin "1") (pinfunction "A_1") (pintype "passive"))
      (node (ref "R17") (pin "2") (pinfunction "2_2") (pintype "passive"))
    )
    (net (code "77") (name "Net-(LED1-K)") (class "Default")
      (node (ref "LED1") (pin "2") (pinfunction "K_2") (pintype "passive"))
      (node (ref "R16") (pin "1") (pinfunction "1_1") (pintype "passive"))
    )
    (net (code "78") (name "Net-(LED2-K)") (class "Default")
      (node (ref "LED2") (pin "2") (pinfunction "K_2") (pintype "passive"))
      (node (ref "R18") (pin "1") (pinfunction "1_1") (pintype "passive"))
    )
    (net (code "79") (name "Net-(LED3-K)") (class "Default")
      (node (ref "LED3") (pin "2") (pinfunction "K_2") (pintype "passive"))
      (node (ref "R19") (pin "1") (pinfunction "1_1") (pintype "passive"))
    )
    (net (code "80") (name "Net-(P4-Pad1)") (class "Default")
      (node (ref "P4") (pin "1") (pinfunction "1_1") (pintype "passive"))
      (node (ref "R11") (pin "1") (pinfunction "1_1") (pintype "passive"))
    )
    (net (code "81") (name "Net-(Q1-D)") (class "Default")
      (node (ref "P4") (pin "2") (pinfunction "2_2") (pintype "passive"))
      (node (ref "Q1") (pin "3") (pinfunction "D_3") (pintype "passive"))
    )
    (net (code "82") (name "Net-(SW1-COMMON)") (class "Default")
      (node (ref "C17") (pin "1") (pinfunction "1_1") (pintype "passive"))
      (node (ref "SW1") (pin "1") (pinfunction "COMMON_1") (pintype "passive"))
      (node (ref "U1") (pin "14") (pinfunction "NRST_14") (pintype "bidirectional"))
    )
    (net (code "83") (name "Net-(U1A-BOOT0)") (class "Default")
      (node (ref "R10") (pin "1") (pinfunction "1_1") (pintype "passive"))
      (node (ref "U1") (pin "94") (pinfunction "BOOT0_94") (pintype "input"))
    )
    (net (code "84") (name "Net-(U1A-PH0-OSC_IN(PH0))") (class "Default")
      (node (ref "C15") (pin "1") (pinfunction "1_1") (pintype "passive"))
      (node (ref "U1") (pin "12") (pinfunction "PH0-OSC_IN(PH0)_12") (pintype "bidirectional"))
      (node (ref "X1") (pin "2") (pinfunction "OSC2_2") (pintype "passive"))
    )
    (net (code "85") (name "Net-(U1A-PH1-OSC_OUT(PH1))") (class "Default")
      (node (ref "C16") (pin "1") (pinfunction "1_1") (pintype "passive"))
      (node (ref "U1") (pin "13") (pinfunction "PH1-OSC_OUT(PH1)_13") (pintype "bidirectional"))
      (node (ref "X1") (pin "1") (pinfunction "OSC1_1") (pintype "passive"))
    )
    (net (code "86") (name "Net-(U1A-VCAP_1)") (class "Default")
      (node (ref "C18") (pin "2") (pinfunction "2_2") (pintype "passive"))
      (node (ref "C19") (pin "2") (pinfunction "2_2") (pintype "passive"))
      (node (ref "U1") (pin "49") (pinfunction "VCAP_1_49") (pintype "power_in"))
      (node (ref "U1") (pin "73") (pinfunction "VCAP_2_73") (pintype "power_in"))
    )
    (net (code "87") (name "Net-(U2-AVDD)") (class "Default")
      (node (ref "C4") (pin "2") (pinfunction "2_2") (pintype "passive"))
      (node (ref "C5") (pin "2") (pinfunction "2_2") (pintype "passive"))
      (node (ref "L1") (pin "2") (pinfunction "2_2") (pintype "passive"))
      (node (ref "U2") (pin "23") (pinfunction "AVDD_23") (pintype "power_in"))
      (node (ref "U2") (pin "7") (pinfunction "CPVDD_7") (pintype "power_in"))
    )
    (net (code "88") (name "Net-(U2-CPCA)") (class "Default")
      (node (ref "C12") (pin "1") (pinfunction "1_1") (pintype "passive"))
      (node (ref "U2") (pin "8") (pinfunction "CPCA_8") (pintype "passive"))
    )
    (net (code "89") (name "Net-(U2-CPCB)") (class "Default")
      (node (ref "C12") (pin "2") (pinfunction "2_2") (pintype "passive"))
      (node (ref "U2") (pin "10") (pinfunction "CPCB_10") (pintype "passive"))
    )
    (net (code "90") (name "Net-(U2-CPVOUTN)") (class "Default")
      (node (ref "C10") (pin "1") (pinfunction "1_1") (pintype "passive"))
      (node (ref "U2") (pin "12") (pinfunction "CPVOUTN_12") (pintype "output"))
    )
    (net (code "91") (name "Net-(U2-CPVOUTP)") (class "Default")
      (node (ref "C11") (pin "2") (pinfunction "2_2") (pintype "passive"))
      (node (ref "U2") (pin "11") (pinfunction "CPVOUTP_11") (pintype "output"))
    )
    (net (code "92") (name "Net-(U2-MICBIAS)") (class "Default")
      (node (ref "C14") (pin "2") (pinfunction "2_2") (pintype "passive"))
      (node (ref "U2") (pin "20") (pinfunction "MICBIAS_20") (pintype "power_in"))
    )
    (net (code "93") (name "unconnected-(P1-Pad3)") (class "Default")
      (node (ref "P1") (pin "3") (pinfunction "3_3") (pintype "passive"))
    )
    (net (code "94") (name "unconnected-(P2-Pad29)") (class "Default")
      (node (ref "P2") (pin "29") (pinfunction "29_29") (pintype "passive"))
    )
    (net (code "95") (name "unconnected-(P2-Pad30)") (class "Default")
      (node (ref "P2") (pin "30") (pinfunction "30_30") (pintype "passive"))
    )
    (net (code "96") (name "unconnected-(S1-MH1-Pad6)") (class "Default")
      (node (ref "S1") (pin "6") (pinfunction "MH1_6") (pintype "passive"))
    )
    (net (code "97") (name "unconnected-(S1-MH2-Pad7)") (class "Default")
      (node (ref "S1") (pin "7") (pinfunction "MH2_7") (pintype "passive"))
    )
    (net (code "98") (name "unconnected-(U1A-PA8-Pad67)") (class "Default")
      (node (ref "U1") (pin "67") (pinfunction "PA8_67") (pintype "bidirectional"))
    )
    (net (code "99") (name "unconnected-(U1A-PA11-Pad70)") (class "Default")
      (node (ref "U1") (pin "70") (pinfunction "PA11_70") (pintype "bidirectional"))
    )
    (net (code "100") (name "unconnected-(U1A-PA12-Pad71)") (class "Default")
      (node (ref "U1") (pin "71") (pinfunction "PA12_71") (pintype "bidirectional"))
    )
    (net (code "101") (name "unconnected-(U1A-PA15(JTDI)-Pad77)") (class "Default")
      (node (ref "U1") (pin "77") (pinfunction "PA15(JTDI)_77") (pintype "bidirectional"))
    )
    (net (code "102") (name "unconnected-(U1A-PB8-Pad95)") (class "Default")
      (node (ref "U1") (pin "95") (pinfunction "PB8_95") (pintype "bidirectional"))
    )
    (net (code "103") (name "unconnected-(U1A-PB9-Pad96)") (class "Default")
      (node (ref "U1") (pin "96") (pinfunction "PB9_96") (pintype "bidirectional"))
    )
    (net (code "104") (name "unconnected-(U1A-PB13-Pad52)") (class "Default")
      (node (ref "U1") (pin "52") (pinfunction "PB13_52") (pintype "bidirectional"))
    )
    (net (code "105") (name "unconnected-(U1A-PC0-Pad15)") (class "Default")
      (node (ref "U1") (pin "15") (pinfunction "PC0_15") (pintype "bidirectional"))
    )
    (net (code "106") (name "unconnected-(U1A-PC1-Pad16)") (class "Default")
      (node (ref "U1") (pin "16") (pinfunction "PC1_16") (pintype "bidirectional"))
    )
    (net (code "107") (name "unconnected-(U1A-PC2-Pad17)") (class "Default")
      (node (ref "U1") (pin "17") (pinfunction "PC2_17") (pintype "bidirectional"))
    )
    (net (code "108") (name "unconnected-(U1A-PC5-Pad34)") (class "Default")
      (node (ref "U1") (pin "34") (pinfunction "PC5_34") (pintype "bidirectional"))
    )
    (net (code "109") (name "unconnected-(U1A-PC13-Pad7)") (class "Default")
      (node (ref "U1") (pin "7") (pinfunction "PC13_7") (pintype "bidirectional"))
    )
    (net (code "110") (name "unconnected-(U1A-PC14-OSC32_IN(PC14)-Pad8)") (class "Default")
      (node (ref "U1") (pin "8") (pinfunction "PC14-OSC32_IN(PC14)_8") (pintype "bidirectional"))
    )
    (net (code "111") (name "unconnected-(U1A-PC15-OSC32_OUT(PC15)-Pad9)") (class "Default")
      (node (ref "U1") (pin "9") (pinfunction "PC15-OSC32_OUT(PC15)_9") (pintype "bidirectional"))
    )
    (net (code "112") (name "unconnected-(U1A-PD3-Pad84)") (class "Default")
      (node (ref "U1") (pin "84") (pinfunction "PD3_84") (pintype "bidirectional"))
    )
    (net (code "113") (name "unconnected-(U1A-PE0-Pad97)") (class "Default")
      (node (ref "U1") (pin "97") (pinfunction "PE0_97") (pintype "bidirectional"))
    )
    (net (code "114") (name "unconnected-(U1A-PE1-Pad98)") (class "Default")
      (node (ref "U1") (pin "98") (pinfunction "PE1_98") (pintype "bidirectional"))
    )
    (net (code "115") (name "unconnected-(U1A-PE6-Pad5)") (class "Default")
      (node (ref "U1") (pin "5") (pinfunction "PE6_5") (pintype "bidirectional"))
    )
    (net (code "116") (name "unconnected-(U2-IN1L{slash}DMICDAT1-Pad27)") (class "Default")
      (node (ref "U2") (pin "27") (pinfunction "IN1L/DMICDAT1_27") (pintype "input"))
    )
    (net (code "117") (name "unconnected-(U2-IN1R{slash}DMICDAT2-Pad25)") (class "Default")
      (node (ref "U2") (pin "25") (pinfunction "IN1R/DMICDAT2_25") (pintype "input"))
    )
    (net (code "118") (name "unconnected-(U2-IN2L-Pad26)") (class "Default")
      (node (ref "U2") (pin "26") (pinfunction "IN2L_26") (pintype "input"))
    )
    (net (code "119") (name "unconnected-(U2-IN2R-Pad24)") (class "Default")
      (node (ref "U2") (pin "24") (pinfunction "IN2R_24") (pintype "input"))
    )
  )
)
